# afe_revA.net
KiCad netlist of a schematic drawn in EAGLE
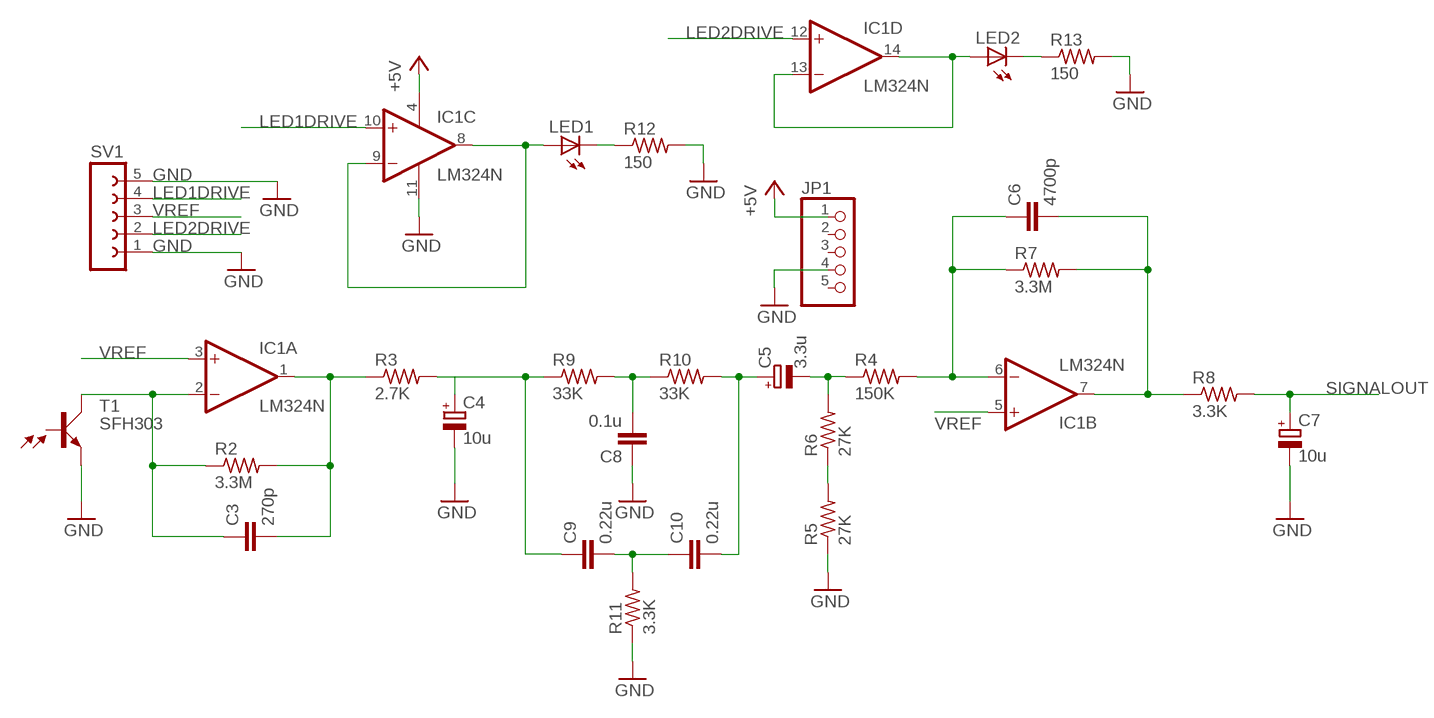
[diagram p0: schematic, sheet 1]

(export (version "E")
  (design (tool "Eeschema 10.0.6"))
  (components
    (comp (ref "C3")
      (value "270p")
      (footprint "eagle-import:C025-024X044")
      (libsource (lib "eagle-import") (part "C-EU025-024X044"))
    )
    (comp (ref "C4")
      (value "10u")
      (footprint "eagle-import:E2,5-5")
      (libsource (lib "eagle-import") (part "CPOL-EUE2.5-5"))
    )
    (comp (ref "C5")
      (value "3.3u")
      (footprint "eagle-import:E2,5-5")
      (libsource (lib "eagle-import") (part "CPOL-EUE2.5-5"))
    )
    (comp (ref "C6")
      (value "4700p")
      (footprint "eagle-import:C025-024X044")
      (libsource (lib "eagle-import") (part "C-EU025-024X044"))
    )
    (comp (ref "C7")
      (value "10u")
      (footprint "eagle-import:E2,5-5")
      (libsource (lib "eagle-import") (part "CPOL-EUE2.5-5"))
    )
    (comp (ref "C8")
      (value "0.1u")
      (footprint "eagle-import:C025-024X044")
      (libsource (lib "eagle-import") (part "C-EU025-024X044"))
    )
    (comp (ref "C9")
      (value "0.22u")
      (footprint "eagle-import:C025-024X044")
      (libsource (lib "eagle-import") (part "C-EU025-024X044"))
    )
    (comp (ref "C10")
      (value "0.22u")
      (footprint "eagle-import:C025-024X044")
      (libsource (lib "eagle-import") (part "C-EU025-024X044"))
    )
    (comp (ref "IC1")
      (value "LM324N")
      (footprint "eagle-import:DIL14")
      (libsource (lib "eagle-import") (part "LM324N"))
    )
    (comp (ref "JP1")
      (value "PINHD-1X5")
      (footprint "eagle-import:1X05")
      (libsource (lib "eagle-import") (part "PINHD-1X5"))
    )
    (comp (ref "LED1")
      (value "LED5MM")
      (footprint "eagle-import:LED5MM")
      (libsource (lib "eagle-import") (part "LED5MM"))
    )
    (comp (ref "LED2")
      (value "LED5MM")
      (footprint "eagle-import:LED5MM")
      (libsource (lib "eagle-import") (part "LED5MM"))
    )
    (comp (ref "R2")
      (value "3.3M")
      (footprint "eagle-import:0204_5")
      (libsource (lib "eagle-import") (part "R-US_0204/5"))
    )
    (comp (ref "R3")
      (value "2.7K")
      (footprint "eagle-import:0204_5")
      (libsource (lib "eagle-import") (part "R-US_0204/5"))
    )
    (comp (ref "R4")
      (value "150K")
      (footprint "eagle-import:0204_5")
      (libsource (lib "eagle-import") (part "R-US_0204/5"))
    )
    (comp (ref "R5")
      (value "27K")
      (footprint "eagle-import:0204_5")
      (libsource (lib "eagle-import") (part "R-US_0204/5"))
    )
    (comp (ref "R6")
      (value "27K")
      (footprint "eagle-import:0204_5")
      (libsource (lib "eagle-import") (part "R-US_0204/5"))
    )
    (comp (ref "R7")
      (value "3.3M")
      (footprint "eagle-import:0204_5")
      (libsource (lib "eagle-import") (part "R-US_0204/5"))
    )
    (comp (ref "R8")
      (value "3.3K")
      (footprint "eagle-import:0204_5")
      (libsource (lib "eagle-import") (part "R-US_0204/5"))
    )
    (comp (ref "R9")
      (value "33K")
      (footprint "eagle-import:0204_5")
      (libsource (lib "eagle-import") (part "R-US_0204/5"))
    )
    (comp (ref "R10")
      (value "33K")
      (footprint "eagle-import:0204_5")
      (libsource (lib "eagle-import") (part "R-US_0204/5"))
    )
    (comp (ref "R11")
      (value "3.3K")
      (footprint "eagle-import:0204_5")
      (libsource (lib "eagle-import") (part "R-US_0204/5"))
    )
    (comp (ref "R12")
      (value "150")
      (footprint "eagle-import:0204_5")
      (libsource (lib "eagle-import") (part "R-US_0204/5"))
    )
    (comp (ref "R13")
      (value "150")
      (footprint "eagle-import:0204_5")
      (libsource (lib "eagle-import") (part "R-US_0204/5"))
    )
    (comp (ref "SV1")
      (value "FE05-1")
      (footprint "eagle-import:FE05-1")
      (libsource (lib "eagle-import") (part "FE05-1"))
    )
    (comp (ref "T1")
      (value "SFH303")
      (footprint "eagle-import:SFH303")
      (libsource (lib "eagle-import") (part "SFH303"))
    )
  )
  (nets
    (net (code "1") (name "+5V") (class "Default")
      (node (ref "IC1") (pin "4") (pinfunction "V+_4") (pintype "power_in"))
      (node (ref "JP1") (pin "1") (pinfunction "1_1") (pintype "passive"))
    )
    (net (code "2") (name "/LED1DRIVE") (class "Default")
      (node (ref "IC1") (pin "10") (pinfunction "+IN_10") (pintype "input"))
      (node (ref "SV1") (pin "4") (pinfunction "4_4") (pintype "passive"))
    )
    (net (code "3") (name "/LED2DRIVE") (class "Default")
      (node (ref "IC1") (pin "12") (pinfunction "+IN_12") (pintype "input"))
      (node (ref "SV1") (pin "2") (pinfunction "2_2") (pintype "passive"))
    )
    (net (code "4") (name "/SIGNALOUT") (class "Default")
      (node (ref "C7") (pin "+") (pinfunction "+_+") (pintype "passive"))
      (node (ref "R8") (pin "2") (pinfunction "2_2") (pintype "passive"))
    )
    (net (code "5") (name "/VREF") (class "Default")
      (node (ref "IC1") (pin "3") (pinfunction "+IN_3") (pintype "input"))
      (node (ref "IC1") (pin "5") (pinfunction "+IN_5") (pintype "input"))
      (node (ref "SV1") (pin "3") (pinfunction "3_3") (pintype "passive"))
    )
    (net (code "6") (name "GND") (class "Default")
      (node (ref "C4") (pin "-") (pinfunction "-_-") (pintype "passive"))
      (node (ref "C7") (pin "-") (pinfunction "-_-") (pintype "passive"))
      (node (ref "C8") (pin "1") (pinfunction "1_1") (pintype "passive"))
      (node (ref "IC1") (pin "11") (pinfunction "V-_11") (pintype "power_in"))
      (node (ref "JP1") (pin "4") (pinfunction "4_4") (pintype "passive"))
      (node (ref "R11") (pin "1") (pinfunction "1_1") (pintype "passive"))
      (node (ref "R12") (pin "2") (pinfunction "2_2") (pintype "passive"))
      (node (ref "R13") (pin "2") (pinfunction "2_2") (pintype "passive"))
      (node (ref "R5") (pin "1") (pinfunction "1_1") (pintype "passive"))
      (node (ref "SV1") (pin "1") (pinfunction "1_1") (pintype "passive"))
      (node (ref "SV1") (pin "5") (pinfunction "5_5") (pintype "passive"))
      (node (ref "T1") (pin "1") (pinfunction "E_1") (pintype "passive"))
    )
    (net (code "7") (name "Net-(C4-Pad+)") (class "Default")
      (node (ref "C4") (pin "+") (pinfunction "+_+") (pintype "passive"))
      (node (ref "C9") (pin "1") (pinfunction "1_1") (pintype "passive"))
      (node (ref "R3") (pin "2") (pinfunction "2_2") (pintype "passive"))
      (node (ref "R9") (pin "1") (pinfunction "1_1") (pintype "passive"))
    )
    (net (code "8") (name "Net-(C5-Pad-)") (class "Default")
      (node (ref "C5") (pin "-") (pinfunction "-_-") (pintype "passive"))
      (node (ref "R4") (pin "1") (pinfunction "1_1") (pintype "passive"))
      (node (ref "R6") (pin "2") (pinfunction "2_2") (pintype "passive"))
    )
    (net (code "9") (name "Net-(C8-Pad2)") (class "Default")
      (node (ref "C8") (pin "2") (pinfunction "2_2") (pintype "passive"))
      (node (ref "R10") (pin "1") (pinfunction "1_1") (pintype "passive"))
      (node (ref "R9") (pin "2") (pinfunction "2_2") (pintype "passive"))
    )
    (net (code "10") (name "Net-(C10-Pad1)") (class "Default")
      (node (ref "C10") (pin "1") (pinfunction "1_1") (pintype "passive"))
      (node (ref "C9") (pin "2") (pinfunction "2_2") (pintype "passive"))
      (node (ref "R11") (pin "2") (pinfunction "2_2") (pintype "passive"))
    )
    (net (code "11") (name "Net-(C10-Pad2)") (class "Default")
      (node (ref "C10") (pin "2") (pinfunction "2_2") (pintype "passive"))
      (node (ref "C5") (pin "+") (pinfunction "+_+") (pintype "passive"))
      (node (ref "R10") (pin "2") (pinfunction "2_2") (pintype "passive"))
    )
    (net (code "12") (name "Net-(IC1A--IN)") (class "Default")
      (node (ref "C3") (pin "1") (pinfunction "1_1") (pintype "passive"))
      (node (ref "IC1") (pin "2") (pinfunction "-IN_2") (pintype "input"))
      (node (ref "R2") (pin "1") (pinfunction "1_1") (pintype "passive"))
      (node (ref "T1") (pin "2") (pinfunction "C_2") (pintype "passive"))
    )
    (net (code "13") (name "Net-(IC1A-OUT)") (class "Default")
      (node (ref "C3") (pin "2") (pinfunction "2_2") (pintype "passive"))
      (node (ref "IC1") (pin "1") (pinfunction "OUT_1") (pintype "output"))
      (node (ref "R2") (pin "2") (pinfunction "2_2") (pintype "passive"))
      (node (ref "R3") (pin "1") (pinfunction "1_1") (pintype "passive"))
    )
    (net (code "14") (name "Net-(IC1B--IN)") (class "Default")
      (node (ref "C6") (pin "1") (pinfunction "1_1") (pintype "passive"))
      (node (ref "IC1") (pin "6") (pinfunction "-IN_6") (pintype "input"))
      (node (ref "R4") (pin "2") (pinfunction "2_2") (pintype "passive"))
      (node (ref "R7") (pin "1") (pinfunction "1_1") (pintype "passive"))
    )
    (net (code "15") (name "Net-(IC1B-OUT)") (class "Default")
      (node (ref "C6") (pin "2") (pinfunction "2_2") (pintype "passive"))
      (node (ref "IC1") (pin "7") (pinfunction "OUT_7") (pintype "output"))
      (node (ref "R7") (pin "2") (pinfunction "2_2") (pintype "passive"))
      (node (ref "R8") (pin "1") (pinfunction "1_1") (pintype "passive"))
    )
    (net (code "16") (name "Net-(IC1C--IN)") (class "Default")
      (node (ref "IC1") (pin "8") (pinfunction "OUT_8") (pintype "output"))
      (node (ref "IC1") (pin "9") (pinfunction "-IN_9") (pintype "input"))
      (node (ref "LED1") (pin "A") (pinfunction "A_A") (pintype "passive"))
    )
    (net (code "17") (name "Net-(IC1D--IN)") (class "Default")
      (node (ref "IC1") (pin "13") (pinfunction "-IN_13") (pintype "input"))
      (node (ref "IC1") (pin "14") (pinfunction "OUT_14") (pintype "output"))
      (node (ref "LED2") (pin "A") (pinfunction "A_A") (pintype "passive"))
    )
    (net (code "18") (name "Net-(LED1-C)") (class "Default")
      (node (ref "LED1") (pin "K") (pinfunction "C_K") (pintype "passive"))
      (node (ref "R12") (pin "1") (pinfunction "1_1") (pintype "passive"))
    )
    (net (code "19") (name "Net-(LED2-C)") (class "Default")
      (node (ref "LED2") (pin "K") (pinfunction "C_K") (pintype "passive"))
      (node (ref "R13") (pin "1") (pinfunction "1_1") (pintype "passive"))
    )
    (net (code "20") (name "Net-(R5-Pad2)") (class "Default")
      (node (ref "R5") (pin "2") (pinfunction "2_2") (pintype "passive"))
      (node (ref "R6") (pin "1") (pinfunction "1_1") (pintype "passive"))
    )
    (net (code "21") (name "unconnected-(JP1-Pad2)") (class "Default")
      (node (ref "JP1") (pin "2") (pinfunction "2_2") (pintype "passive"))
    )
    (net (code "22") (name "unconnected-(JP1-Pad3)") (class "Default")
      (node (ref "JP1") (pin "3") (pinfunction "3_3") (pintype "passive"))
    )
    (net (code "23") (name "unconnected-(JP1-Pad5)") (class "Default")
      (node (ref "JP1") (pin "5") (pinfunction "5_5") (pintype "passive"))
    )
    (net (code "24") (name "unconnected-(T1-B-Pad3)") (class "Default")
      (node (ref "T1") (pin "3") (pinfunction "B_3") (pintype "passive"))
    )
  )
)
